# boardShildSchematic.net
KiCad netlist of a schematic drawn in EAGLE
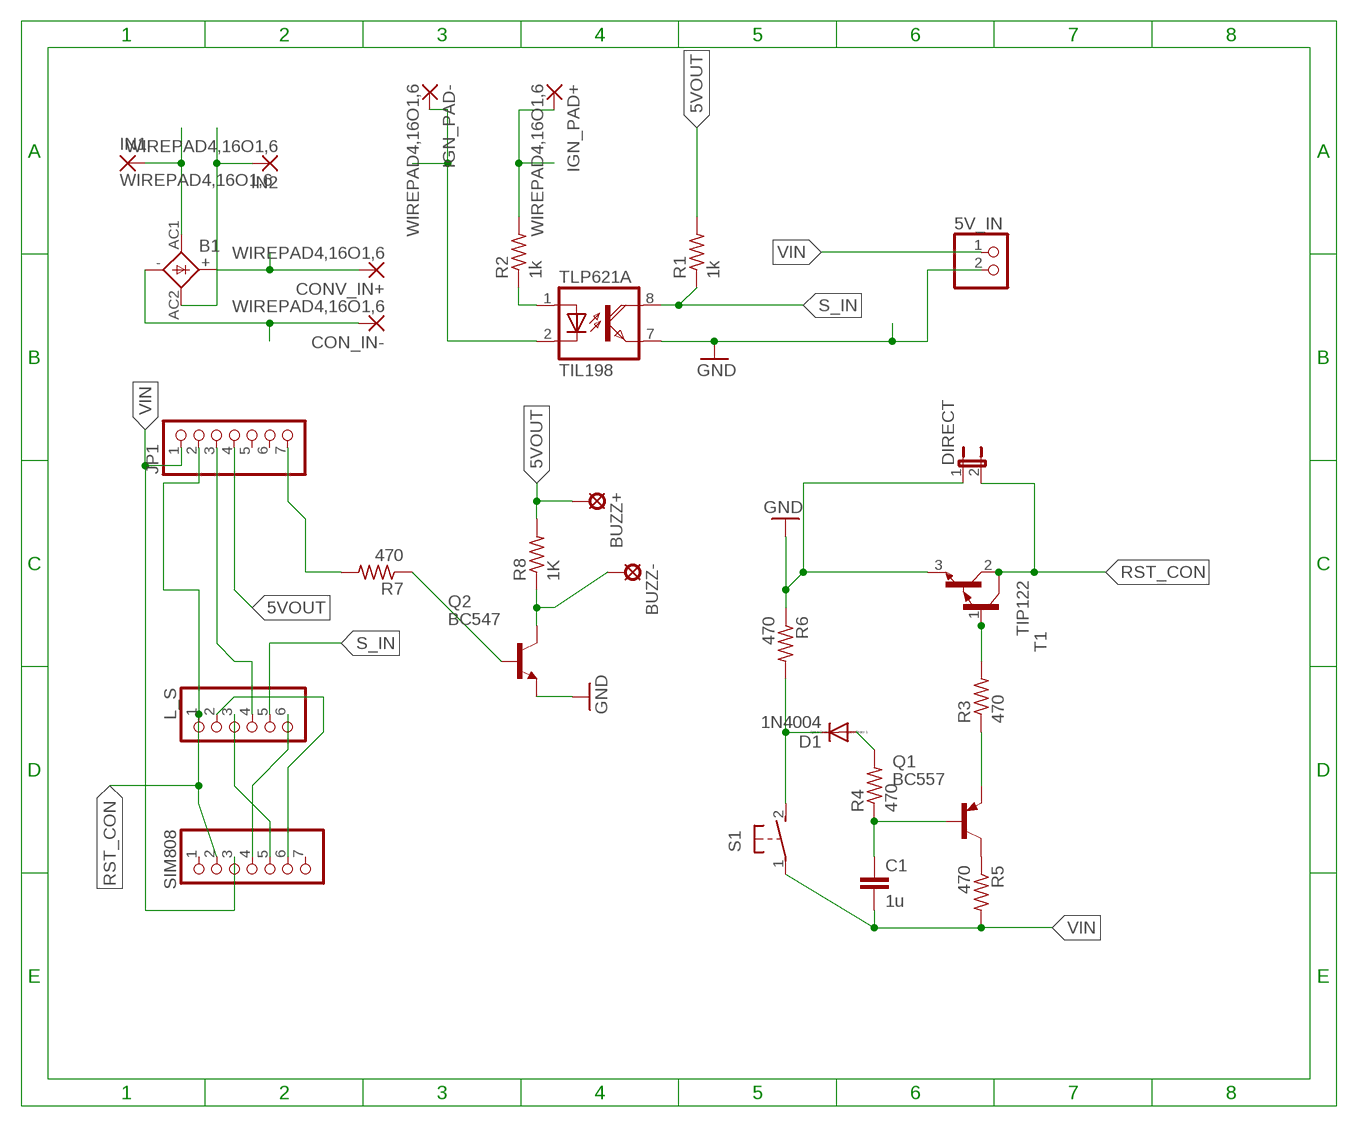
[diagram p0: schematic, sheet 1]

(export (version "E")
  (design (tool "Eeschema 10.0.6"))
  (components
    (comp (ref "5V_IN")
      (value "PINHD-1X2")
      (footprint "eagle-import:1X02")
      (libsource (lib "eagle-import") (part "PINHD-1X2"))
    )
    (comp (ref "B1")
      (value "FB15")
      (footprint "eagle-import:FB15")
      (libsource (lib "eagle-import") (part "FB15"))
    )
    (comp (ref "BUZZ+")
      (value "LSP10")
      (footprint "eagle-import:LSP10")
      (libsource (lib "eagle-import") (part "LSP10"))
    )
    (comp (ref "BUZZ-")
      (value "LSP10")
      (footprint "eagle-import:LSP10")
      (libsource (lib "eagle-import") (part "LSP10"))
    )
    (comp (ref "C1")
      (value "1u")
      (footprint "eagle-import:C2.5-5")
      (libsource (lib "eagle-import") (part "C2.5/5"))
    )
    (comp (ref "CONV_IN+")
      (value "WIREPAD4,16O1,6")
      (footprint "eagle-import:4,16O1,6")
      (libsource (lib "eagle-import") (part "WIREPAD4,16O1,6"))
    )
    (comp (ref "CON_IN-")
      (value "WIREPAD4,16O1,6")
      (footprint "eagle-import:4,16O1,6")
      (libsource (lib "eagle-import") (part "WIREPAD4,16O1,6"))
    )
    (comp (ref "D1")
      (value "1N4004")
      (footprint "eagle-import:DO41-10")
      (libsource (lib "eagle-import") (part "1N4004"))
    )
    (comp (ref "DIRECT")
      (value "JP1E")
      (footprint "eagle-import:JP1")
      (libsource (lib "eagle-import") (part "JP1E"))
    )
    (comp (ref "IGN_PAD+")
      (value "WIREPAD4,16O1,6")
      (footprint "eagle-import:4,16O1,6")
      (libsource (lib "eagle-import") (part "WIREPAD4,16O1,6"))
    )
    (comp (ref "IGN_PAD-")
      (value "WIREPAD4,16O1,6")
      (footprint "eagle-import:4,16O1,6")
      (libsource (lib "eagle-import") (part "WIREPAD4,16O1,6"))
    )
    (comp (ref "IN1")
      (value "WIREPAD4,16O1,6")
      (footprint "eagle-import:4,16O1,6")
      (libsource (lib "eagle-import") (part "WIREPAD4,16O1,6"))
    )
    (comp (ref "IN2")
      (value "WIREPAD4,16O1,6")
      (footprint "eagle-import:4,16O1,6")
      (libsource (lib "eagle-import") (part "WIREPAD4,16O1,6"))
    )
    (comp (ref "JP1")
      (value "PINHD-1X7")
      (footprint "eagle-import:1X07")
      (libsource (lib "eagle-import") (part "PINHD-1X7"))
    )
    (comp (ref "L_S")
      (value "PINHD-1X6")
      (footprint "eagle-import:1X06")
      (libsource (lib "eagle-import") (part "PINHD-1X6"))
    )
    (comp (ref "Q1")
      (value "BC557")
      (footprint "eagle-import:TO92")
      (libsource (lib "eagle-import") (part "BC557"))
    )
    (comp (ref "Q2")
      (value "BC547")
      (footprint "eagle-import:TO92")
      (libsource (lib "eagle-import") (part "BC547"))
    )
    (comp (ref "R1")
      (value "1k")
      (footprint "eagle-import:0204_5")
      (libsource (lib "eagle-import") (part "R-US_0204/5"))
    )
    (comp (ref "R2")
      (value "1k")
      (footprint "eagle-import:0204_5")
      (libsource (lib "eagle-import") (part "R-US_0204/5"))
    )
    (comp (ref "R3")
      (value "470")
      (footprint "eagle-import:0204_5")
      (libsource (lib "eagle-import") (part "R-US_0204/5"))
    )
    (comp (ref "R4")
      (value "470")
      (footprint "eagle-import:0204_5")
      (libsource (lib "eagle-import") (part "R-US_0204/5"))
    )
    (comp (ref "R5")
      (value "470")
      (footprint "eagle-import:0204_5")
      (libsource (lib "eagle-import") (part "R-US_0204/5"))
    )
    (comp (ref "R6")
      (value "470")
      (footprint "eagle-import:0204_5")
      (libsource (lib "eagle-import") (part "R-US_0204/5"))
    )
    (comp (ref "R7")
      (value "470")
      (footprint "eagle-import:0204_5")
      (libsource (lib "eagle-import") (part "R-US_0204/5"))
    )
    (comp (ref "R8")
      (value "1K")
      (footprint "eagle-import:0204_5")
      (libsource (lib "eagle-import") (part "R-US_0204/5"))
    )
    (comp (ref "S1")
      (value "31-XX")
      (footprint "eagle-import:B3F-31XX")
      (fields (field (name "MPN") "B3F-3100"))
      (libsource (lib "eagle-import") (part "31-XX"))
    )
    (comp (ref "SIM808")
      (value "PINHD-1X7")
      (footprint "eagle-import:1X07")
      (libsource (lib "eagle-import") (part "PINHD-1X7"))
    )
    (comp (ref "T1")
      (value "TIP122")
      (footprint "eagle-import:TO220")
      (libsource (lib "eagle-import") (part "TIP122"))
    )
    (comp (ref "TLP621")
      (value "TIL198")
      (footprint "eagle-import:DIL08")
      (libsource (lib "eagle-import") (part "TIL198"))
    )
  )
  (nets
    (net (code "1") (name "5VOUT") (class "Default")
      (node (ref "BUZZ+") (pin "MP") (pinfunction "MP_MP") (pintype "passive"))
      (node (ref "JP1") (pin "4") (pinfunction "4_4") (pintype "passive"))
      (node (ref "R1") (pin "2") (pinfunction "2_2") (pintype "passive"))
      (node (ref "R8") (pin "2") (pinfunction "2_2") (pintype "passive"))
    )
    (net (code "2") (name "GND") (class "Default")
      (node (ref "5V_IN") (pin "2") (pinfunction "2_2") (pintype "passive"))
      (node (ref "DIRECT") (pin "1") (pinfunction "1_1") (pintype "passive"))
      (node (ref "Q2") (pin "1") (pinfunction "E_1") (pintype "passive"))
      (node (ref "R6") (pin "1") (pinfunction "1_1") (pintype "passive"))
      (node (ref "T1") (pin "3") (pinfunction "E_3") (pintype "passive"))
      (node (ref "TLP621") (pin "7") (pinfunction "EMI_7") (pintype "passive"))
    )
    (net (code "3") (name "Net-(CONV_IN+-P)") (class "Default")
      (node (ref "B1") (pin "+") (pinfunction "+_+") (pintype "passive"))
      (node (ref "CONV_IN+") (pin "1") (pinfunction "P_1") (pintype "passive"))
    )
    (net (code "4") (name "Net-(CON_IN--P)") (class "Default")
      (node (ref "B1") (pin "-") (pinfunction "-_-") (pintype "passive"))
      (node (ref "CON_IN-") (pin "1") (pinfunction "P_1") (pintype "passive"))
    )
    (net (code "5") (name "Net-(D1-PadA)") (class "Default")
      (node (ref "D1") (pin "A") (pinfunction "A_A") (pintype "passive"))
      (node (ref "R4") (pin "2") (pinfunction "2_2") (pintype "passive"))
    )
    (net (code "6") (name "Net-(IGN_PAD+-P)") (class "Default")
      (node (ref "IGN_PAD+") (pin "1") (pinfunction "P_1") (pintype "passive"))
      (node (ref "R2") (pin "2") (pinfunction "2_2") (pintype "passive"))
    )
    (net (code "7") (name "Net-(IGN_PAD--P)") (class "Default")
      (node (ref "IGN_PAD-") (pin "1") (pinfunction "P_1") (pintype "passive"))
      (node (ref "TLP621") (pin "2") (pinfunction "C_2") (pintype "passive"))
    )
    (net (code "8") (name "Net-(IN1-P)") (class "Default")
      (node (ref "B1") (pin "AC1") (pinfunction "AC1_AC1") (pintype "passive"))
      (node (ref "IN1") (pin "1") (pinfunction "P_1") (pintype "passive"))
    )
    (net (code "9") (name "Net-(IN2-P)") (class "Default")
      (node (ref "B1") (pin "AC2") (pinfunction "AC2_AC2") (pintype "passive"))
      (node (ref "IN2") (pin "1") (pinfunction "P_1") (pintype "passive"))
    )
    (net (code "10") (name "Net-(JP1-Pad3)") (class "Default")
      (node (ref "JP1") (pin "3") (pinfunction "3_3") (pintype "passive"))
      (node (ref "L_S") (pin "4") (pinfunction "4_4") (pintype "passive"))
    )
    (net (code "11") (name "Net-(JP1-Pad7)") (class "Default")
      (node (ref "JP1") (pin "7") (pinfunction "7_7") (pintype "passive"))
      (node (ref "R7") (pin "2") (pinfunction "2_2") (pintype "passive"))
    )
    (net (code "12") (name "Net-(L_S-Pad2)") (class "Default")
      (node (ref "L_S") (pin "2") (pinfunction "2_2") (pintype "passive"))
      (node (ref "SIM808") (pin "6") (pinfunction "6_6") (pintype "passive"))
    )
    (net (code "13") (name "Net-(L_S-Pad3)") (class "Default")
      (node (ref "L_S") (pin "3") (pinfunction "3_3") (pintype "passive"))
      (node (ref "SIM808") (pin "5") (pinfunction "5_5") (pintype "passive"))
    )
    (net (code "14") (name "Net-(L_S-Pad6)") (class "Default")
      (node (ref "L_S") (pin "6") (pinfunction "6_6") (pintype "passive"))
      (node (ref "SIM808") (pin "4") (pinfunction "4_4") (pintype "passive"))
    )
    (net (code "15") (name "Net-(Q1-B)") (class "Default")
      (node (ref "C1") (pin "1") (pinfunction "1_1") (pintype "passive"))
      (node (ref "Q1") (pin "2") (pinfunction "B_2") (pintype "passive"))
      (node (ref "R4") (pin "1") (pinfunction "1_1") (pintype "passive"))
    )
    (net (code "16") (name "Net-(Q1-C)") (class "Default")
      (node (ref "Q1") (pin "3") (pinfunction "C_3") (pintype "passive"))
      (node (ref "R5") (pin "1") (pinfunction "1_1") (pintype "passive"))
    )
    (net (code "17") (name "Net-(Q1-E)") (class "Default")
      (node (ref "Q1") (pin "1") (pinfunction "E_1") (pintype "passive"))
      (node (ref "R3") (pin "1") (pinfunction "1_1") (pintype "passive"))
    )
    (net (code "18") (name "Net-(Q2-B)") (class "Default")
      (node (ref "Q2") (pin "2") (pinfunction "B_2") (pintype "passive"))
      (node (ref "R7") (pin "1") (pinfunction "1_1") (pintype "passive"))
    )
    (net (code "19") (name "Net-(Q2-C)") (class "Default")
      (node (ref "BUZZ-") (pin "MP") (pinfunction "MP_MP") (pintype "passive"))
      (node (ref "Q2") (pin "3") (pinfunction "C_3") (pintype "passive"))
      (node (ref "R8") (pin "1") (pinfunction "1_1") (pintype "passive"))
    )
    (net (code "20") (name "Net-(S1-S)") (class "Default")
      (node (ref "D1") (pin "C") (pinfunction "C_C") (pintype "passive"))
      (node (ref "R6") (pin "2") (pinfunction "2_2") (pintype "passive"))
      (node (ref "S1") (pin "2") (pinfunction "S_2") (pintype "passive"))
    )
    (net (code "21") (name "Net-(T1-B)") (class "Default")
      (node (ref "R3") (pin "2") (pinfunction "2_2") (pintype "passive"))
      (node (ref "T1") (pin "1") (pinfunction "B_1") (pintype "passive"))
    )
    (net (code "22") (name "Net-(TLP621A-A)") (class "Default")
      (node (ref "R2") (pin "1") (pinfunction "1_1") (pintype "passive"))
      (node (ref "TLP621") (pin "1") (pinfunction "A_1") (pintype "passive"))
    )
    (net (code "23") (name "RST_CON") (class "Default")
      (node (ref "DIRECT") (pin "2") (pinfunction "2_2") (pintype "passive"))
      (node (ref "JP1") (pin "2") (pinfunction "2_2") (pintype "passive"))
      (node (ref "L_S") (pin "1") (pinfunction "1_1") (pintype "passive"))
      (node (ref "SIM808") (pin "2") (pinfunction "2_2") (pintype "passive"))
      (node (ref "T1") (pin "2") (pinfunction "C_2") (pintype "passive"))
    )
    (net (code "24") (name "S_IN") (class "Default")
      (node (ref "L_S") (pin "5") (pinfunction "5_5") (pintype "passive"))
      (node (ref "R1") (pin "1") (pinfunction "1_1") (pintype "passive"))
      (node (ref "TLP621") (pin "8") (pinfunction "COL_8") (pintype "passive"))
    )
    (net (code "25") (name "VIN") (class "Default")
      (node (ref "5V_IN") (pin "1") (pinfunction "1_1") (pintype "passive"))
      (node (ref "C1") (pin "2") (pinfunction "2_2") (pintype "passive"))
      (node (ref "JP1") (pin "1") (pinfunction "1_1") (pintype "passive"))
      (node (ref "R5") (pin "2") (pinfunction "2_2") (pintype "passive"))
      (node (ref "S1") (pin "1") (pinfunction "P_1") (pintype "passive"))
      (node (ref "SIM808") (pin "3") (pinfunction "3_3") (pintype "passive"))
    )
    (net (code "26") (name "unconnected-(JP1-Pad5)") (class "Default")
      (node (ref "JP1") (pin "5") (pinfunction "5_5") (pintype "passive"))
    )
    (net (code "27") (name "unconnected-(JP1-Pad6)") (class "Default")
      (node (ref "JP1") (pin "6") (pinfunction "6_6") (pintype "passive"))
    )
    (net (code "28") (name "unconnected-(SIM808-Pad1)") (class "Default")
      (node (ref "SIM808") (pin "1") (pinfunction "1_1") (pintype "passive"))
    )
    (net (code "29") (name "unconnected-(SIM808-Pad7)") (class "Default")
      (node (ref "SIM808") (pin "7") (pinfunction "7_7") (pintype "passive"))
    )
  )
)
